# Icarus_Som.net
KiCad netlist of a schematic drawn in Altium Designer
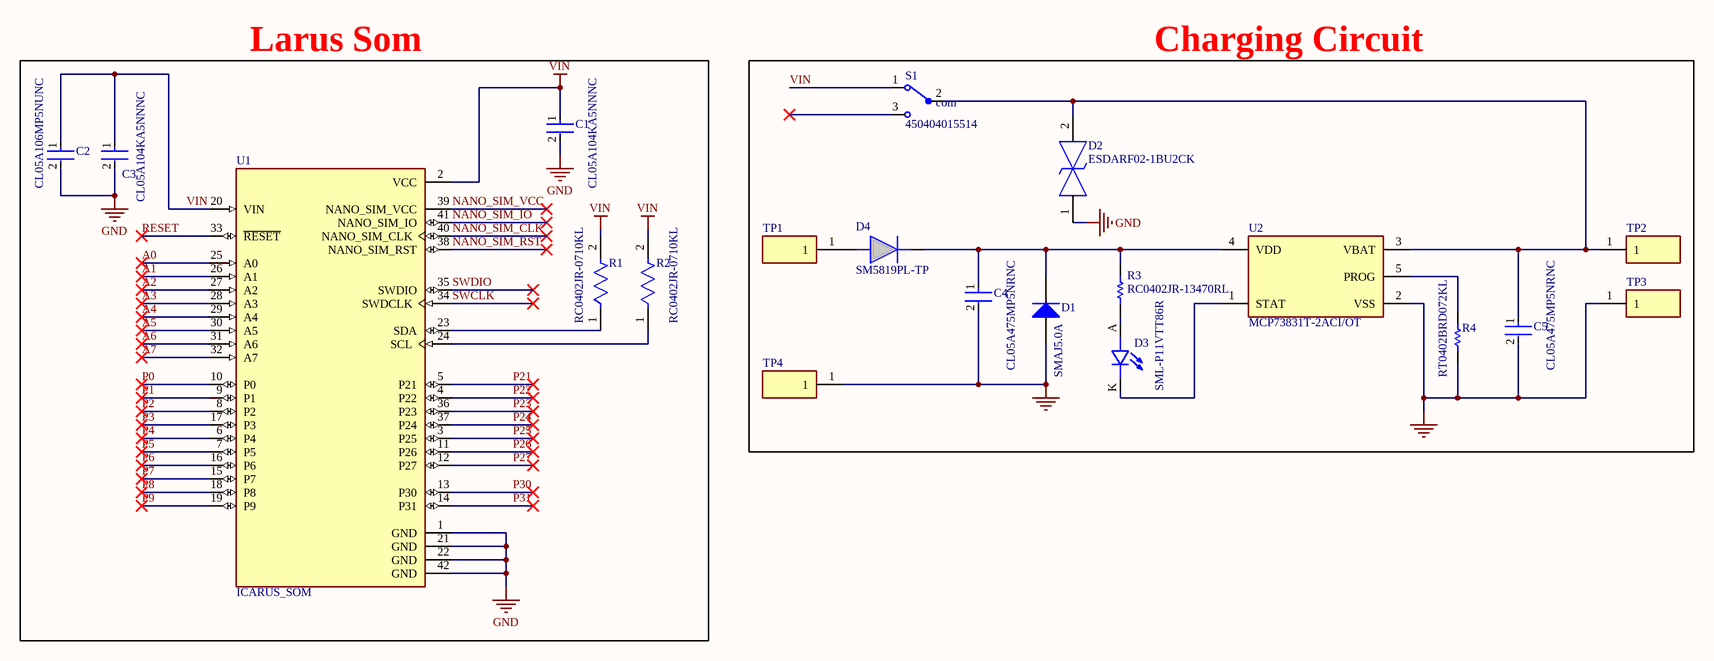
[diagram p0: Icarus Som.SchDoc]

(export (version "E")
  (design (tool "Eeschema 10.0.6"))
  (components
    (comp (ref "C1")
      (value "CL05A104KA5NNNC")
      (footprint "FP-CL278-IPC_A")
      (description "Cap Ceramic 100nF 25V X5R ±10% SMD 0402 +85°C Paper T/R")
      (fields (field (name "VOLTAGE") "25V") (field (name "TOLERANCE") "10%"))
      (libsource (lib "Icarus Sch_Lib") (part "CMP-13271-000728-1"))
    )
    (comp (ref "C2")
      (value "CL05A106MP5NUNC")
      (footprint "FP-CL05A106MP5NUNC-MFG")
      (description "CAP CER 10UF 10V X5R 0402")
      (fields
        (field (name "OCTOPART") "https://octopart.com/cl05a106mp5nunc-samsung-22457395")
        (field (name "TOLERANCE") "20%")
      )
      (libsource (lib "Icarus Sch_Lib") (part "CMP-13271-000002-1"))
    )
    (comp (ref "C3")
      (value "CL05A104KA5NNNC")
      (footprint "FP-CL278-IPC_A")
      (description "Cap Ceramic 100nF 25V X5R ±10% SMD 0402 +85°C Paper T/R")
      (fields (field (name "VOLTAGE") "25V") (field (name "TOLERANCE") "10%"))
      (libsource (lib "Icarus Sch_Lib") (part "CMP-13271-000728-1"))
    )
    (comp (ref "C4")
      (value "CL05A475MP5NRNC")
      (footprint "FP-CL282-IPC_A")
      (description "Cap Ceramic 4.7uF 10V X5R ±20% SMD 0402 +85°C Paper T/R")
      (fields (field (name "TOLERANCE") "20%"))
      (libsource (lib "Icarus Sch_Lib") (part "CMP-13271-000548-1"))
    )
    (comp (ref "C5")
      (value "CL05A475MP5NRNC")
      (footprint "FP-CL282-IPC_A")
      (description "Cap Ceramic 4.7uF 10V X5R ±20% SMD 0402 +85°C Paper T/R")
      (fields (field (name "TOLERANCE") "20%"))
      (libsource (lib "Icarus Sch_Lib") (part "CMP-13271-000548-1"))
    )
    (comp (ref "D1")
      (value "SMAJ5.0A")
      (footprint "BOUR-SMA-2_V")
      (fields (field (name "MANUFACTURER") "Bourns"))
      (libsource (lib "Icarus Sch_Lib") (part "CMP-2000-07090-1"))
    )
    (comp (ref "D2")
      (value "ESDARF02-1BU2CK")
      (footprint "ESDARF021BU2CK")
      (description "STMicroelectronics ESDARF02-1BU2CK Bi-Directional ESD Protection Diode, 20W peak, 2-Pin ST-0201")
      (fields (field (name "MOUSER PART NUMBER") "511-ESDARF02-1BU2CK"))
      (libsource (lib "Icarus Sch_Lib") (part "ESDARF02-1BU2CK"))
    )
    (comp (ref "D3")
      (value "SML-P11VTT86R")
      (footprint "LED_SML-P11VTT86R")
      (description "Red 626nm LED Indication - Discrete 1.8V 0402 (1006 Metric)")
      (fields (field (name "MF") "Rohm") (field (name "DIGI-KEY_PART_NUMBER") "846-SML-P11VTT86RTR-ND"))
      (libsource (lib "Icarus Sch_Lib") (part "SML-P11VTT86R"))
    )
    (comp (ref "D4")
      (value "SM5819PL-TP")
      (footprint "SODFL3716X120N")
      (description "Schottky Barrier Rectifiers")
      (fields (field (name "MOUSER PART NUMBER") "833-SM5819PL-TP"))
      (libsource (lib "Icarus Sch_Lib") (part "SM5819PL-TP"))
    )
    (comp (ref "R1")
      (value "RC0402JR-0710KL")
      (footprint "FP-RC0402-0_4-IPC_A")
      (description "RES 10K OHM 5% 1/16W 0402")
      (fields (field (name "TOLERANCE") "5%"))
      (libsource (lib "Icarus Sch_Lib") (part "CMP-2002-07915-3"))
    )
    (comp (ref "R2")
      (value "RC0402JR-0710KL")
      (footprint "FP-RC0402-0_4-IPC_A")
      (description "RES 10K OHM 5% 1/16W 0402")
      (fields (field (name "TOLERANCE") "5%"))
      (libsource (lib "Icarus Sch_Lib") (part "CMP-2002-07915-3"))
    )
    (comp (ref "R3")
      (value "RC0402JR-13470RL")
      (footprint "RESC1005X40X25LL05T10")
      (description "RES 470R")
      (fields (field (name "MANUFACTURER") "Yageo"))
      (libsource (lib "Icarus Sch_Lib") (part "CMP-2002-08087-1"))
    )
    (comp (ref "R4")
      (value "RT0402BRD072KL")
      (footprint "RESC1005X35X25LL10T10")
      (description "RES 2K")
      (fields (field (name "MANUFACTURER") "Yageo"))
      (libsource (lib "Icarus Sch_Lib") (part "CMP-2002-02941-1"))
    )
    (comp (ref "S1")
      (value "450404015514")
      (footprint "450404015514")
      (description "MINI SLIDE SWITCH 6.7 X 2.7 MM.")
      (fields (field (name "MF") "WÃ¼rth Elektronik"))
      (libsource (lib "Icarus Sch_Lib") (part "450404015514"))
    )
    (comp (ref "TP1")
      (value "~")
      (footprint "Icarus PCB_Lib:TP+195X110")
      (description "Natural PC Test Point - - Plating Surface Mount Mounting Type")
      (fields (field (name "MF") "TE Connectivity AMP Connectors") (field (name "MP") "RCU-0C"))
      (libsource (lib "") (part "RCU-0C_1"))
    )
    (comp (ref "TP2")
      (value "~")
      (footprint "Icarus PCB_Lib:TP+195X110")
      (description "Natural PC Test Point - - Plating Surface Mount Mounting Type")
      (fields (field (name "MF") "TE Connectivity AMP Connectors") (field (name "MP") "RCU-0C"))
      (libsource (lib "Icarus Sch_Lib") (part "RCU-0C"))
    )
    (comp (ref "TP3")
      (value "~")
      (footprint "Icarus PCB_Lib:TP+195X110")
      (description "Natural PC Test Point - - Plating Surface Mount Mounting Type")
      (fields (field (name "MF") "TE Connectivity AMP Connectors") (field (name "MP") "RCU-0C"))
      (libsource (lib "Icarus Sch_Lib") (part "RCU-0C"))
    )
    (comp (ref "TP4")
      (value "~")
      (footprint "Icarus PCB_Lib:TP+195X110")
      (description "Natural PC Test Point - - Plating Surface Mount Mounting Type")
      (fields (field (name "MF") "TE Connectivity AMP Connectors") (field (name "MP") "RCU-0C"))
      (libsource (lib "") (part "RCU-0C_1"))
    )
    (comp (ref "U1")
      (value "ICARUS_SOM")
      (footprint "MODULE_ICARUS_SOM")
      (fields (field (name "MP") "Icarus SOM") (field (name "MF") "Actinius"))
      (libsource (lib "Icarus Sch_Lib") (part "ICARUS_SOM"))
    )
    (comp (ref "U2")
      (value "MCP73831T-2ACI/OT")
      (footprint "FP-C04-091-OT-IPC_A")
      (description "IC CONTROLLR LI-ION 4.2V SOT23-5")
      (libsource (lib "Icarus Sch_Lib") (part "CMP-0133-00143-2"))
    )
  )
  (nets
    (net (code "1") (name "/A0") (class "Default")
      (node (ref "U1") (pin "25") (pinfunction "A0_25") (pintype "input+no_connect"))
    )
    (net (code "2") (name "/A1") (class "Default")
      (node (ref "U1") (pin "26") (pinfunction "A1_26") (pintype "input+no_connect"))
    )
    (net (code "3") (name "/A2") (class "Default")
      (node (ref "U1") (pin "27") (pinfunction "A2_27") (pintype "input+no_connect"))
    )
    (net (code "4") (name "/A3") (class "Default")
      (node (ref "U1") (pin "28") (pinfunction "A3_28") (pintype "input+no_connect"))
    )
    (net (code "5") (name "/A4") (class "Default")
      (node (ref "U1") (pin "29") (pinfunction "A4_29") (pintype "input+no_connect"))
    )
    (net (code "6") (name "/A5") (class "Default")
      (node (ref "U1") (pin "30") (pinfunction "A5_30") (pintype "input+no_connect"))
    )
    (net (code "7") (name "/A6") (class "Default")
      (node (ref "U1") (pin "31") (pinfunction "A6_31") (pintype "input+no_connect"))
    )
    (net (code "8") (name "/A7") (class "Default")
      (node (ref "U1") (pin "32") (pinfunction "A7_32") (pintype "input+no_connect"))
    )
    (net (code "9") (name "/NANO_SIM_CLK") (class "Default")
      (node (ref "U1") (pin "40") (pinfunction "NANO_SIM_CLK_40") (pintype "bidirectional+no_connect"))
    )
    (net (code "10") (name "/NANO_SIM_IO") (class "Default")
      (node (ref "U1") (pin "41") (pinfunction "NANO_SIM_IO_41") (pintype "bidirectional+no_connect"))
    )
    (net (code "11") (name "/NANO_SIM_RST") (class "Default")
      (node (ref "U1") (pin "38") (pinfunction "NANO_SIM_RST_38") (pintype "bidirectional+no_connect"))
    )
    (net (code "12") (name "/NANO_SIM_VCC") (class "Default")
      (node (ref "U1") (pin "39") (pinfunction "NANO_SIM_VCC_39") (pintype "power_in+no_connect"))
    )
    (net (code "13") (name "/P0") (class "Default")
      (node (ref "U1") (pin "10") (pinfunction "P0_10") (pintype "bidirectional+no_connect"))
    )
    (net (code "14") (name "/P1") (class "Default")
      (node (ref "U1") (pin "9") (pinfunction "P1_9") (pintype "bidirectional+no_connect"))
    )
    (net (code "15") (name "/P2") (class "Default")
      (node (ref "U1") (pin "8") (pinfunction "P2_8") (pintype "bidirectional+no_connect"))
    )
    (net (code "16") (name "/P3") (class "Default")
      (node (ref "U1") (pin "17") (pinfunction "P3_17") (pintype "bidirectional+no_connect"))
    )
    (net (code "17") (name "/P4") (class "Default")
      (node (ref "U1") (pin "6") (pinfunction "P4_6") (pintype "bidirectional+no_connect"))
    )
    (net (code "18") (name "/P5") (class "Default")
      (node (ref "U1") (pin "7") (pinfunction "P5_7") (pintype "bidirectional+no_connect"))
    )
    (net (code "19") (name "/P6") (class "Default")
      (node (ref "U1") (pin "16") (pinfunction "P6_16") (pintype "bidirectional+no_connect"))
    )
    (net (code "20") (name "/P7") (class "Default")
      (node (ref "U1") (pin "15") (pinfunction "P7_15") (pintype "bidirectional+no_connect"))
    )
    (net (code "21") (name "/P8") (class "Default")
      (node (ref "U1") (pin "18") (pinfunction "P8_18") (pintype "bidirectional+no_connect"))
    )
    (net (code "22") (name "/P9") (class "Default")
      (node (ref "U1") (pin "19") (pinfunction "P9_19") (pintype "bidirectional+no_connect"))
    )
    (net (code "23") (name "/P21") (class "Default")
      (node (ref "U1") (pin "5") (pinfunction "P21_5") (pintype "bidirectional+no_connect"))
    )
    (net (code "24") (name "/P22") (class "Default")
      (node (ref "U1") (pin "4") (pinfunction "P22_4") (pintype "bidirectional+no_connect"))
    )
    (net (code "25") (name "/P23") (class "Default")
      (node (ref "U1") (pin "36") (pinfunction "P23_36") (pintype "bidirectional+no_connect"))
    )
    (net (code "26") (name "/P24") (class "Default")
      (node (ref "U1") (pin "37") (pinfunction "P24_37") (pintype "bidirectional+no_connect"))
    )
    (net (code "27") (name "/P25") (class "Default")
      (node (ref "U1") (pin "3") (pinfunction "P25_3") (pintype "bidirectional+no_connect"))
    )
    (net (code "28") (name "/P26") (class "Default")
      (node (ref "U1") (pin "11") (pinfunction "P26_11") (pintype "bidirectional+no_connect"))
    )
    (net (code "29") (name "/P27") (class "Default")
      (node (ref "U1") (pin "12") (pinfunction "P27_12") (pintype "bidirectional+no_connect"))
    )
    (net (code "30") (name "/P30") (class "Default")
      (node (ref "U1") (pin "13") (pinfunction "P30_13") (pintype "bidirectional+no_connect"))
    )
    (net (code "31") (name "/P31") (class "Default")
      (node (ref "U1") (pin "14") (pinfunction "P31_14") (pintype "bidirectional+no_connect"))
    )
    (net (code "32") (name "/RESET") (class "Default")
      (node (ref "U1") (pin "33") (pinfunction "~{RESET}_33") (pintype "bidirectional+no_connect"))
    )
    (net (code "33") (name "/SWCLK") (class "Default")
      (node (ref "U1") (pin "34") (pinfunction "SWDCLK_34") (pintype "input+no_connect"))
    )
    (net (code "34") (name "/SWDIO") (class "Default")
      (node (ref "U1") (pin "35") (pinfunction "SWDIO_35") (pintype "bidirectional+no_connect"))
    )
    (net (code "35") (name "GND") (class "Default")
      (node (ref "C1") (pin "2") (pinfunction "2_2") (pintype "passive"))
      (node (ref "C2") (pin "2") (pinfunction "2_2") (pintype "passive"))
      (node (ref "C3") (pin "2") (pinfunction "2_2") (pintype "passive"))
      (node (ref "C4") (pin "2") (pinfunction "2_2") (pintype "passive"))
      (node (ref "C5") (pin "2") (pinfunction "2_2") (pintype "passive"))
      (node (ref "D1") (pin "1") (pinfunction "A_1") (pintype "passive"))
      (node (ref "D2") (pin "1") (pinfunction "1_1") (pintype "passive"))
      (node (ref "R4") (pin "1") (pinfunction "1_1") (pintype "passive"))
      (node (ref "TP3") (pin "1") (pinfunction "1_1") (pintype "passive"))
      (node (ref "TP4") (pin "1") (pinfunction "1_1") (pintype "passive"))
      (node (ref "U1") (pin "1") (pinfunction "GND_1") (pintype "power_in"))
      (node (ref "U1") (pin "21") (pinfunction "GND_21") (pintype "power_in"))
      (node (ref "U1") (pin "22") (pinfunction "GND_22") (pintype "power_in"))
      (node (ref "U1") (pin "42") (pinfunction "GND_42") (pintype "power_in"))
      (node (ref "U2") (pin "2") (pinfunction "VSS_2") (pintype "power_in"))
    )
    (net (code "36") (name "Net-(D1-K)") (class "Default")
      (node (ref "C4") (pin "1") (pinfunction "1_1") (pintype "passive"))
      (node (ref "D1") (pin "2") (pinfunction "K_2") (pintype "passive"))
      (node (ref "D4") (pin "1") (pinfunction "K_1") (pintype "passive"))
      (node (ref "R3") (pin "2") (pinfunction "2_2") (pintype "passive"))
      (node (ref "U2") (pin "4") (pinfunction "VDD_4") (pintype "power_in"))
    )
    (net (code "37") (name "Net-(D3-PadA)") (class "Default")
      (node (ref "D3") (pin "A") (pinfunction "A_A") (pintype "passive"))
      (node (ref "R3") (pin "1") (pinfunction "1_1") (pintype "passive"))
    )
    (net (code "38") (name "Net-(D4-A)") (class "Default")
      (node (ref "D4") (pin "2") (pinfunction "A_2") (pintype "passive"))
      (node (ref "TP1") (pin "1") (pinfunction "1_1") (pintype "passive"))
    )
    (net (code "39") (name "Net-(U1-SCL)") (class "Default")
      (node (ref "R2") (pin "1") (pinfunction "1_1") (pintype "passive"))
      (node (ref "U1") (pin "24") (pinfunction "SCL_24") (pintype "input"))
    )
    (net (code "40") (name "Net-(U1-SDA)") (class "Default")
      (node (ref "R1") (pin "1") (pinfunction "1_1") (pintype "passive"))
      (node (ref "U1") (pin "23") (pinfunction "SDA_23") (pintype "bidirectional"))
    )
    (net (code "41") (name "Net-(U2-PROG)") (class "Default")
      (node (ref "R4") (pin "2") (pinfunction "2_2") (pintype "passive"))
      (node (ref "U2") (pin "5") (pinfunction "PROG_5") (pintype "passive"))
    )
    (net (code "42") (name "Net-(U2-STAT)") (class "Default")
      (node (ref "D3") (pin "K") (pinfunction "K_K") (pintype "passive"))
      (node (ref "U2") (pin "1") (pinfunction "STAT_1") (pintype "passive"))
    )
    (net (code "43") (name "Net-(U2-VBAT)") (class "Default")
      (node (ref "C5") (pin "1") (pinfunction "1_1") (pintype "passive"))
      (node (ref "D2") (pin "2") (pinfunction "2_2") (pintype "passive"))
      (node (ref "S1") (pin "2") (pinfunction "2_2") (pintype "passive"))
      (node (ref "TP2") (pin "1") (pinfunction "1_1") (pintype "passive"))
      (node (ref "U2") (pin "3") (pinfunction "VBAT_3") (pintype "power_in"))
    )
    (net (code "44") (name "VIN") (class "Default")
      (node (ref "C1") (pin "1") (pinfunction "1_1") (pintype "passive"))
      (node (ref "C2") (pin "1") (pinfunction "1_1") (pintype "passive"))
      (node (ref "C3") (pin "1") (pinfunction "1_1") (pintype "passive"))
      (node (ref "R1") (pin "2") (pinfunction "2_2") (pintype "passive"))
      (node (ref "R2") (pin "2") (pinfunction "2_2") (pintype "passive"))
      (node (ref "S1") (pin "1") (pinfunction "1_1") (pintype "passive"))
      (node (ref "U1") (pin "2") (pinfunction "VCC_2") (pintype "power_in"))
      (node (ref "U1") (pin "20") (pinfunction "VIN_20") (pintype "input"))
    )
    (net (code "45") (name "unconnected-(S1-Pad3)") (class "Default")
      (node (ref "S1") (pin "3") (pinfunction "3_3") (pintype "passive+no_connect"))
    )
  )
)
